# ESP8266_RFID_Schematic.net
KiCad netlist of a schematic drawn in EAGLE
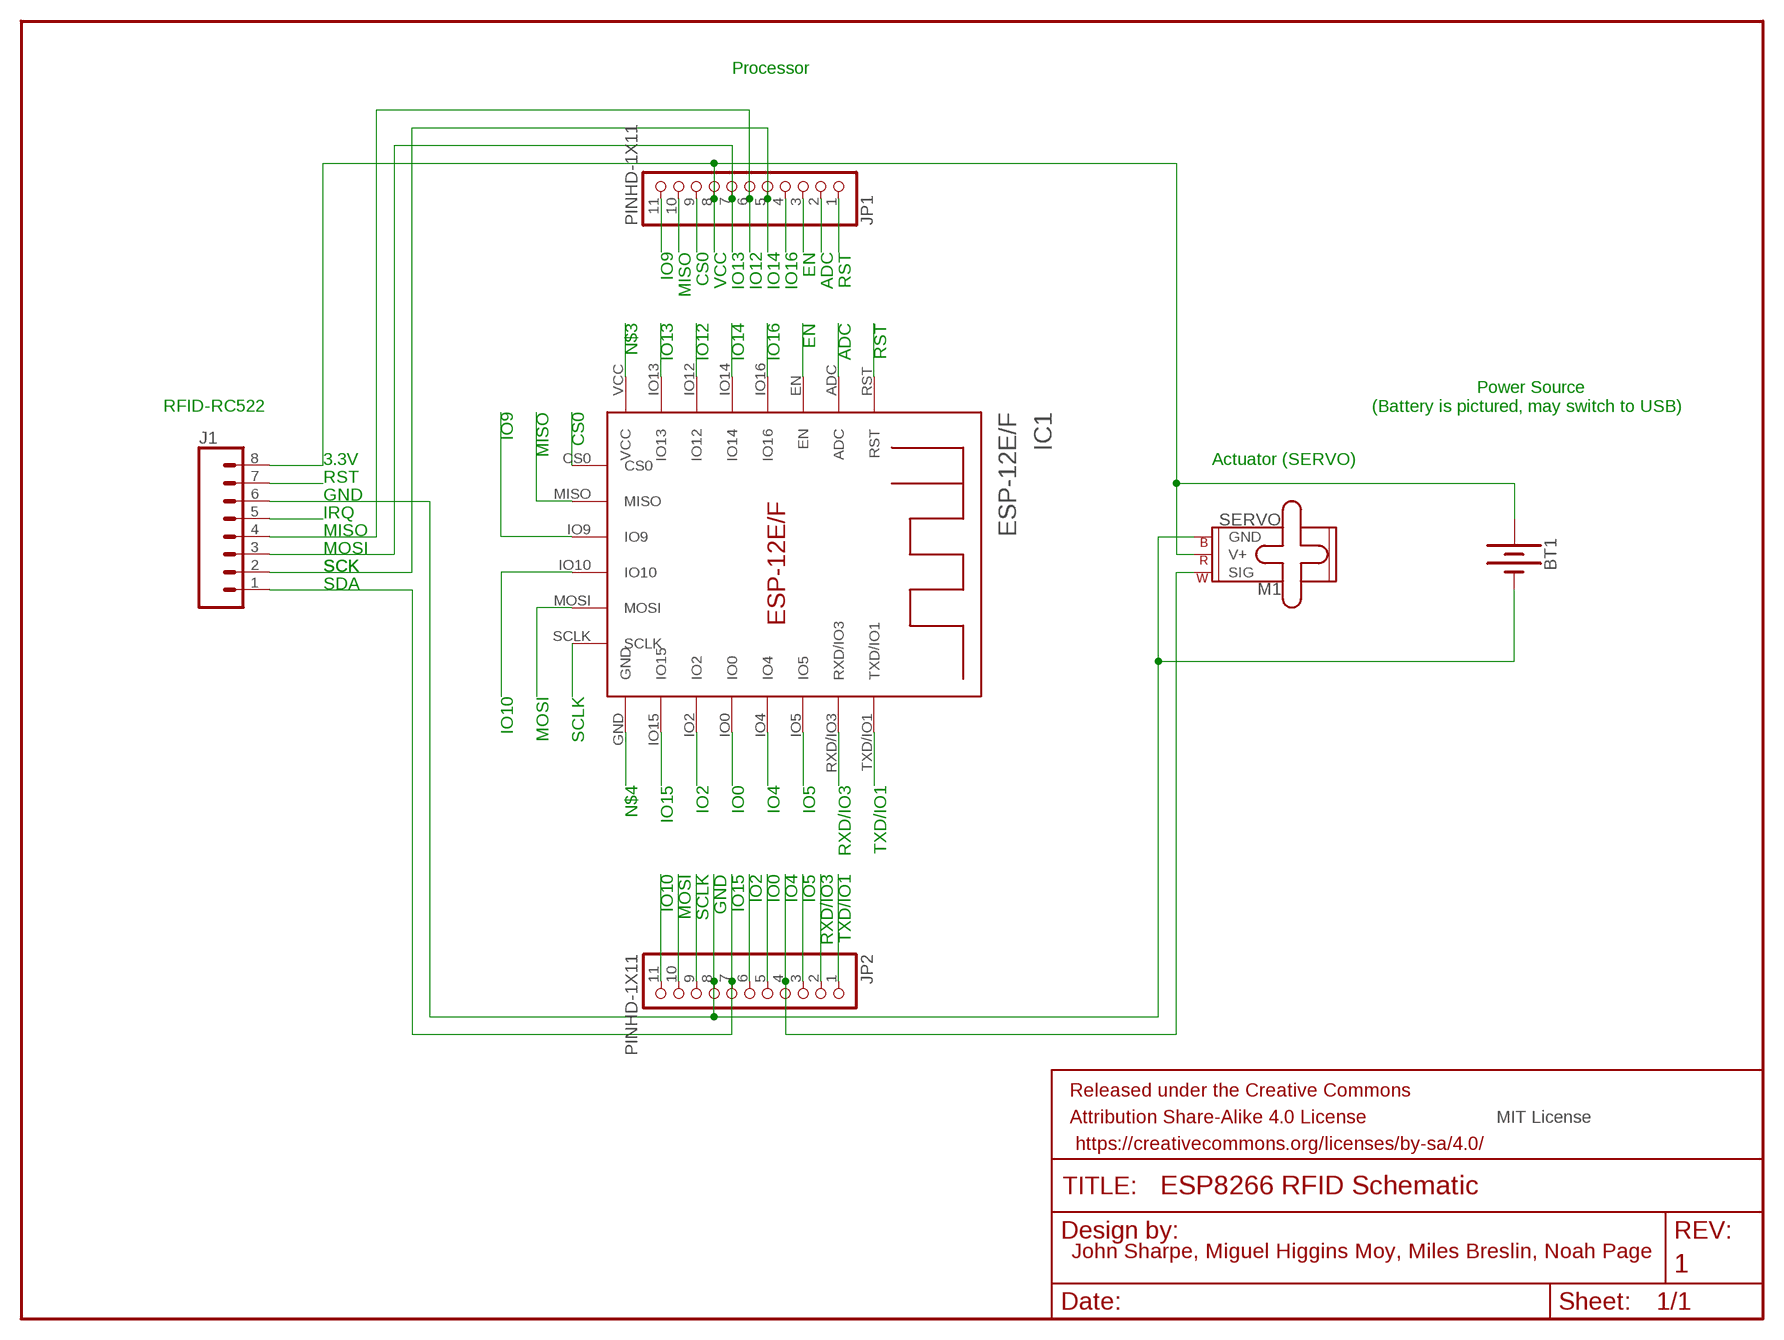
[diagram p0: schematic, sheet 1]

(export (version "E")
  (design (tool "Eeschema 10.0.6"))
  (components
    (comp (ref "BT1")
      (value "BATTERY-AA")
      (footprint "eagle-import:BATTERY-AA")
      (libsource (lib "eagle-import") (part "BATTERY-AA"))
    )
    (comp (ref "FRAME1")
      (value "FRAME-LETTER")
      (footprint "eagle-import:CREATIVE_COMMONS")
      (fields
        (field (name "DESIGNER") "John Sharpe, Miguel Higgins Moy, Miles Breslin, Noah Page")
        (field (name "LICENSE") "MIT License")
        (field (name "REV") "1")
      )
      (libsource (lib "eagle-import") (part "FRAME-LETTER"))
    )
    (comp (ref "IC1")
      (value "ESP-12E/F")
      (footprint "eagle-import:ESP-12E")
      (libsource (lib "eagle-import") (part "ESP-12E/F"))
    )
    (comp (ref "J1")
      (value "CONN_08\"")
      (footprint "eagle-import:1X08")
      (libsource (lib "eagle-import") (part "CONN_08{dblquote}"))
    )
    (comp (ref "JP1")
      (value "PINHD-1X11")
      (footprint "eagle-import:1X11")
      (libsource (lib "eagle-import") (part "PINHD-1X11"))
    )
    (comp (ref "JP2")
      (value "PINHD-1X11")
      (footprint "eagle-import:1X11")
      (libsource (lib "eagle-import") (part "PINHD-1X11"))
    )
    (comp (ref "M1")
      (value "SERVO")
      (footprint "eagle-import:1X03")
      (libsource (lib "eagle-import") (part "SERVO"))
    )
  )
  (nets
    (net (code "1") (name "/ADC") (class "Default")
      (node (ref "IC1") (pin "ADC") (pinfunction "ADC_ADC") (pintype "bidirectional"))
      (node (ref "JP1") (pin "2") (pinfunction "2_2") (pintype "passive"))
    )
    (net (code "2") (name "/CS0") (class "Default")
      (node (ref "IC1") (pin "CS0") (pinfunction "CS0_CS0") (pintype "bidirectional"))
      (node (ref "JP1") (pin "9") (pinfunction "9_9") (pintype "passive"))
    )
    (net (code "3") (name "/EN") (class "Default")
      (node (ref "IC1") (pin "EN") (pinfunction "EN_EN") (pintype "bidirectional"))
      (node (ref "JP1") (pin "3") (pinfunction "3_3") (pintype "passive"))
    )
    (net (code "4") (name "/GND") (class "Default")
      (node (ref "BT1") (pin "GND@1") (pinfunction "-_GND@1") (pintype "power_in"))
      (node (ref "J1") (pin "6") (pinfunction "6_6") (pintype "passive"))
      (node (ref "JP2") (pin "8") (pinfunction "8_8") (pintype "passive"))
      (node (ref "M1") (pin "3") (pinfunction "GND_3") (pintype "bidirectional"))
    )
    (net (code "5") (name "/IO0") (class "Default")
      (node (ref "IC1") (pin "IO0") (pinfunction "IO0_IO0") (pintype "bidirectional"))
      (node (ref "JP2") (pin "5") (pinfunction "5_5") (pintype "passive"))
    )
    (net (code "6") (name "/IO2") (class "Default")
      (node (ref "IC1") (pin "IO2") (pinfunction "IO2_IO2") (pintype "bidirectional"))
      (node (ref "JP2") (pin "6") (pinfunction "6_6") (pintype "passive"))
    )
    (net (code "7") (name "/IO4") (class "Default")
      (node (ref "IC1") (pin "IO4") (pinfunction "IO4_IO4") (pintype "bidirectional"))
      (node (ref "JP2") (pin "4") (pinfunction "4_4") (pintype "passive"))
      (node (ref "M1") (pin "1") (pinfunction "SIG_1") (pintype "bidirectional"))
    )
    (net (code "8") (name "/IO5") (class "Default")
      (node (ref "IC1") (pin "IO5") (pinfunction "IO5_IO5") (pintype "bidirectional"))
      (node (ref "JP2") (pin "3") (pinfunction "3_3") (pintype "passive"))
    )
    (net (code "9") (name "/IO9") (class "Default")
      (node (ref "IC1") (pin "IO9") (pinfunction "IO9_IO9") (pintype "bidirectional"))
      (node (ref "JP1") (pin "11") (pinfunction "11_11") (pintype "passive"))
    )
    (net (code "10") (name "/IO10") (class "Default")
      (node (ref "IC1") (pin "IO10") (pinfunction "IO10_IO10") (pintype "bidirectional"))
      (node (ref "JP2") (pin "11") (pinfunction "11_11") (pintype "passive"))
    )
    (net (code "11") (name "/IO12") (class "Default")
      (node (ref "J1") (pin "4") (pinfunction "4_4") (pintype "passive"))
      (node (ref "JP1") (pin "6") (pinfunction "6_6") (pintype "passive"))
    )
    (net (code "12") (name "/IO13") (class "Default")
      (node (ref "IC1") (pin "IO13") (pinfunction "IO13_IO13") (pintype "bidirectional"))
      (node (ref "J1") (pin "3") (pinfunction "3_3") (pintype "passive"))
      (node (ref "JP1") (pin "7") (pinfunction "7_7") (pintype "passive"))
    )
    (net (code "13") (name "/IO14") (class "Default")
      (node (ref "J1") (pin "2") (pinfunction "2_2") (pintype "passive"))
      (node (ref "JP1") (pin "5") (pinfunction "5_5") (pintype "passive"))
    )
    (net (code "14") (name "/IO15") (class "Default")
      (node (ref "J1") (pin "1") (pinfunction "1_1") (pintype "passive"))
      (node (ref "JP2") (pin "7") (pinfunction "7_7") (pintype "passive"))
    )
    (net (code "15") (name "/IO16") (class "Default")
      (node (ref "IC1") (pin "IO16") (pinfunction "IO16_IO16") (pintype "bidirectional"))
      (node (ref "JP1") (pin "4") (pinfunction "4_4") (pintype "passive"))
    )
    (net (code "16") (name "/MISO") (class "Default")
      (node (ref "IC1") (pin "MISO") (pinfunction "MISO_MISO") (pintype "bidirectional"))
      (node (ref "JP1") (pin "10") (pinfunction "10_10") (pintype "passive"))
    )
    (net (code "17") (name "/MOSI") (class "Default")
      (node (ref "IC1") (pin "MOSI") (pinfunction "MOSI_MOSI") (pintype "bidirectional"))
      (node (ref "JP2") (pin "10") (pinfunction "10_10") (pintype "passive"))
    )
    (net (code "18") (name "/N$3") (class "Default")
      (node (ref "IC1") (pin "VCC") (pinfunction "VCC_VCC") (pintype "power_in"))
    )
    (net (code "19") (name "/N$4") (class "Default")
      (node (ref "IC1") (pin "GND") (pinfunction "GND_GND") (pintype "power_in"))
    )
    (net (code "20") (name "/RST") (class "Default")
      (node (ref "IC1") (pin "RST") (pinfunction "RST_RST") (pintype "input"))
      (node (ref "J1") (pin "7") (pinfunction "7_7") (pintype "passive"))
      (node (ref "JP1") (pin "1") (pinfunction "1_1") (pintype "passive"))
    )
    (net (code "21") (name "/RXD{slash}IO3") (class "Default")
      (node (ref "IC1") (pin "RXD/IO3") (pinfunction "RXD/IO3_RXD/IO3") (pintype "bidirectional"))
      (node (ref "JP2") (pin "2") (pinfunction "2_2") (pintype "passive"))
    )
    (net (code "22") (name "/SCLK") (class "Default")
      (node (ref "IC1") (pin "SCLK") (pinfunction "SCLK_SCLK") (pintype "bidirectional"))
      (node (ref "JP2") (pin "9") (pinfunction "9_9") (pintype "passive"))
    )
    (net (code "23") (name "/TXD{slash}IO1") (class "Default")
      (node (ref "IC1") (pin "TXD/IO1") (pinfunction "TXD/IO1_TXD/IO1") (pintype "bidirectional"))
      (node (ref "JP2") (pin "1") (pinfunction "1_1") (pintype "passive"))
    )
    (net (code "24") (name "/VCC") (class "Default")
      (node (ref "BT1") (pin "PWR@1") (pinfunction "+_PWR@1") (pintype "power_in"))
      (node (ref "J1") (pin "8") (pinfunction "8_8") (pintype "passive"))
      (node (ref "JP1") (pin "8") (pinfunction "8_8") (pintype "passive"))
      (node (ref "M1") (pin "2") (pinfunction "V+_2") (pintype "bidirectional"))
    )
    (net (code "25") (name "unconnected-(IC1-PadIO12)") (class "Default")
      (node (ref "IC1") (pin "IO12") (pinfunction "IO12_IO12") (pintype "bidirectional"))
    )
    (net (code "26") (name "unconnected-(IC1-PadIO14)") (class "Default")
      (node (ref "IC1") (pin "IO14") (pinfunction "IO14_IO14") (pintype "bidirectional"))
    )
    (net (code "27") (name "unconnected-(IC1-PadIO15)") (class "Default")
      (node (ref "IC1") (pin "IO15") (pinfunction "IO15_IO15") (pintype "bidirectional"))
    )
    (net (code "28") (name "unconnected-(J1-Pad5)") (class "Default")
      (node (ref "J1") (pin "5") (pinfunction "5_5") (pintype "passive"))
    )
  )
)
